# jtag-adapter-1-4.net
KiCad netlist of a schematic drawn in EAGLE
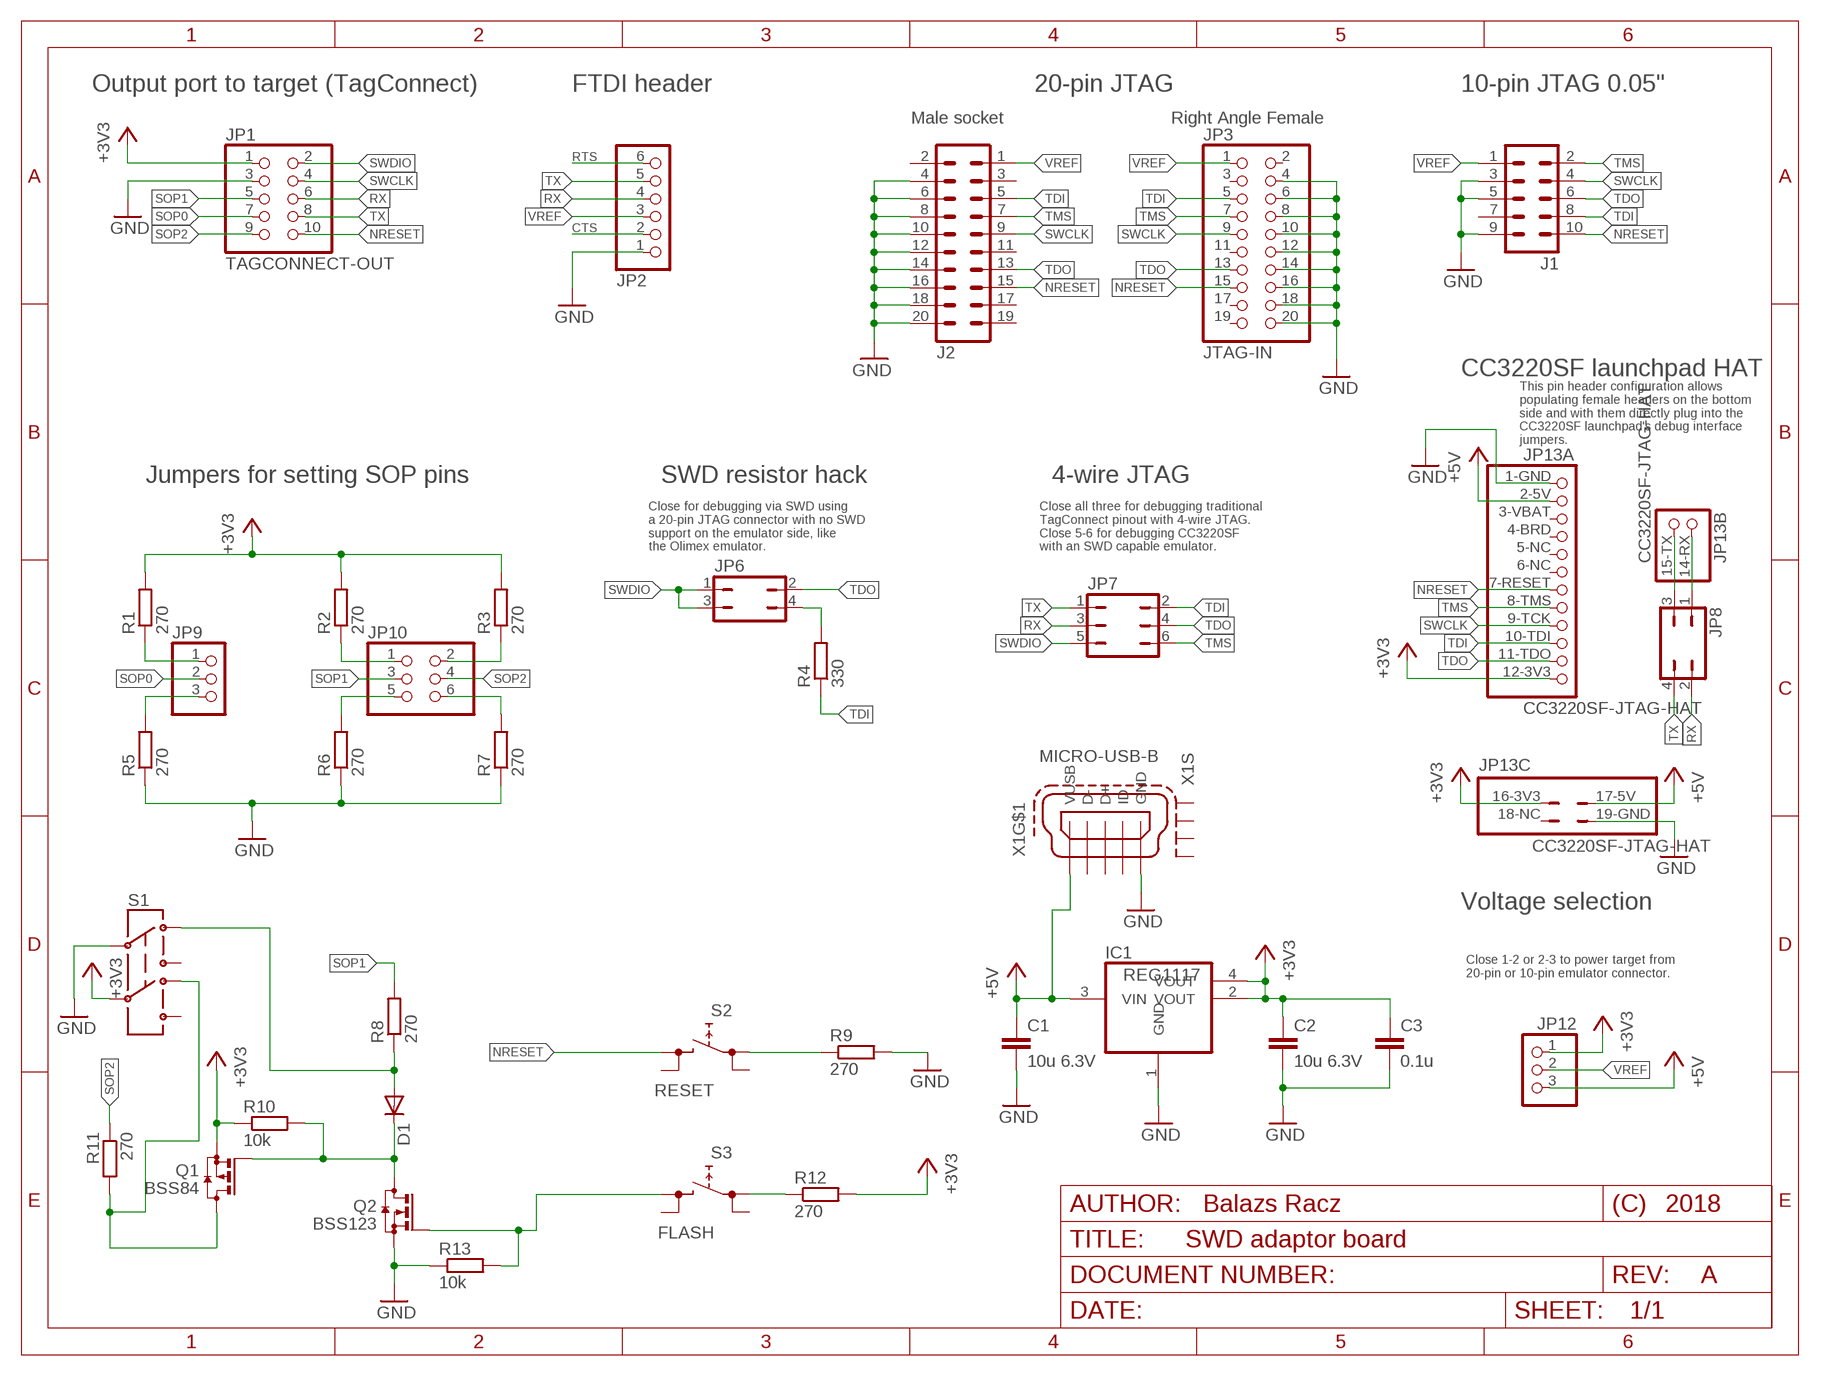
[diagram p0: schematic, sheet 1]

(export (version "E")
  (design (tool "Eeschema 10.0.6"))
  (components
    (comp (ref "C1")
      (value "10u 6.3V")
      (footprint "eagle-import:C0603K")
      (libsource (lib "eagle-import") (part "C-EUC0603K"))
    )
    (comp (ref "C2")
      (value "10u 6.3V")
      (footprint "eagle-import:C0603K")
      (libsource (lib "eagle-import") (part "C-EUC0603K"))
    )
    (comp (ref "C3")
      (value "0.1u")
      (footprint "eagle-import:C0603K")
      (libsource (lib "eagle-import") (part "C-EUC0603K"))
    )
    (comp (ref "D1")
      (value "DIODE-MINIMELF")
      (footprint "eagle-import:MINIMELF")
      (libsource (lib "eagle-import") (part "DIODE-MINIMELF"))
    )
    (comp (ref "IC1")
      (value "REG1117")
      (footprint "eagle-import:SOT223")
      (libsource (lib "eagle-import") (part "REG1117"))
    )
    (comp (ref "J1")
      (value "MA05-2_0.05X0.05")
      (footprint "eagle-import:MA05-2_0.05_X_0.05")
      (libsource (lib "eagle-import") (part "MA05-2_0.05X0.05"))
    )
    (comp (ref "J2")
      (value "MA10-2S")
      (footprint "eagle-import:MA10-2-SHROUDED")
      (libsource (lib "eagle-import") (part "MA10-2S"))
    )
    (comp (ref "JP1")
      (value "TAGCONNECT-OUT")
      (footprint "eagle-import:CON10M")
      (libsource (lib "eagle-import") (part "PINHD-2X5CN"))
    )
    (comp (ref "JP2")
      (value "PINHD-1X6")
      (footprint "eagle-import:1X06")
      (libsource (lib "eagle-import") (part "PINHD-1X6"))
    )
    (comp (ref "JP3")
      (value "JTAG-IN")
      (footprint "eagle-import:2X10_90")
      (libsource (lib "eagle-import") (part "PINHD-2X10/90"))
    )
    (comp (ref "JP6")
      (value "JP2Q")
      (footprint "eagle-import:JP2Q")
      (libsource (lib "eagle-import") (part "trainlib_JP2Q"))
    )
    (comp (ref "JP7")
      (value "JP3Q")
      (footprint "eagle-import:JP3Q")
      (libsource (lib "eagle-import") (part "JP3Q"))
    )
    (comp (ref "JP8")
      (value "JP2Q")
      (footprint "eagle-import:JP2Q")
      (libsource (lib "eagle-import") (part "JP2Q"))
    )
    (comp (ref "JP9")
      (value "PINHD-1X3")
      (footprint "eagle-import:1X03")
      (libsource (lib "eagle-import") (part "PINHD-1X3"))
    )
    (comp (ref "JP10")
      (value "PINHD-2X3")
      (footprint "eagle-import:2X03")
      (libsource (lib "eagle-import") (part "PINHD-2X3"))
    )
    (comp (ref "JP12")
      (value "PINHD-1X3")
      (footprint "eagle-import:1X03")
      (libsource (lib "eagle-import") (part "PINHD-1X3"))
    )
    (comp (ref "JP13")
      (value "CC3220SF-JTAG-HAT")
      (footprint "eagle-import:JTAG-LAUNCHPAD-3220SF")
      (libsource (lib "eagle-import") (part "CC3220SF-JTAG-HAT"))
    )
    (comp (ref "Q1")
      (value "BSS84")
      (footprint "eagle-import:SOT23")
      (libsource (lib "eagle-import") (part "BSS84"))
    )
    (comp (ref "Q2")
      (value "BSS123")
      (footprint "eagle-import:SOT23")
      (libsource (lib "eagle-import") (part "BSS123"))
    )
    (comp (ref "R1")
      (value "270")
      (footprint "eagle-import:R0805")
      (libsource (lib "eagle-import") (part "R-EU_R0805"))
    )
    (comp (ref "R2")
      (value "270")
      (footprint "eagle-import:R0805")
      (libsource (lib "eagle-import") (part "R-EU_R0805"))
    )
    (comp (ref "R3")
      (value "270")
      (footprint "eagle-import:R0805")
      (libsource (lib "eagle-import") (part "R-EU_R0805"))
    )
    (comp (ref "R4")
      (value "330")
      (footprint "eagle-import:R0805")
      (libsource (lib "eagle-import") (part "R-EU_R0805"))
    )
    (comp (ref "R5")
      (value "270")
      (footprint "eagle-import:R0805")
      (libsource (lib "eagle-import") (part "R-EU_R0805"))
    )
    (comp (ref "R6")
      (value "270")
      (footprint "eagle-import:R0805")
      (libsource (lib "eagle-import") (part "R-EU_R0805"))
    )
    (comp (ref "R7")
      (value "270")
      (footprint "eagle-import:R0805")
      (libsource (lib "eagle-import") (part "R-EU_R0805"))
    )
    (comp (ref "R8")
      (value "270")
      (footprint "eagle-import:R0805")
      (libsource (lib "eagle-import") (part "R-EU_R0805"))
    )
    (comp (ref "R9")
      (value "270")
      (footprint "eagle-import:R0805")
      (libsource (lib "eagle-import") (part "R-EU_R0805"))
    )
    (comp (ref "R10")
      (value "10k")
      (footprint "eagle-import:R0805")
      (libsource (lib "eagle-import") (part "R-EU_R0805"))
    )
    (comp (ref "R11")
      (value "270")
      (footprint "eagle-import:R0805")
      (libsource (lib "eagle-import") (part "R-EU_R0805"))
    )
    (comp (ref "R12")
      (value "270")
      (footprint "eagle-import:R0805")
      (libsource (lib "eagle-import") (part "R-EU_R0805"))
    )
    (comp (ref "R13")
      (value "10k")
      (footprint "eagle-import:R0805")
      (libsource (lib "eagle-import") (part "R-EU_R0805"))
    )
    (comp (ref "S1")
      (value "SWITCH-DPDTJS202011CQN")
      (footprint "eagle-import:DPDT-2.5X3.2MM")
      (libsource (lib "eagle-import") (part "SWITCH-DPDTJS202011CQN"))
    )
    (comp (ref "S2")
      (value "RESET")
      (footprint "eagle-import:TACTSW-6X6")
      (libsource (lib "eagle-import") (part "TACTSW-6X6S"))
    )
    (comp (ref "S3")
      (value "FLASH")
      (footprint "eagle-import:TACTSW-6X6")
      (libsource (lib "eagle-import") (part "TACTSW-6X6S"))
    )
    (comp (ref "X1")
      (value "MICRO-USB-B")
      (footprint "eagle-import:MICRO-B-PAC")
      (libsource (lib "eagle-import") (part "MICRO-USB-B"))
    )
  )
  (nets
    (net (code "1") (name "+3V3") (class "Default")
      (node (ref "C2") (pin "1") (pinfunction "1_1") (pintype "passive"))
      (node (ref "C3") (pin "1") (pinfunction "1_1") (pintype "passive"))
      (node (ref "IC1") (pin "2") (pinfunction "VOUT_2") (pintype "output"))
      (node (ref "IC1") (pin "4") (pinfunction "VOUT_4") (pintype "output"))
      (node (ref "JP1") (pin "1") (pinfunction "1_1") (pintype "passive"))
      (node (ref "JP12") (pin "1") (pinfunction "1_1") (pintype "passive"))
      (node (ref "JP13") (pin "12-3V3") (pinfunction "12_12-3V3") (pintype "passive"))
      (node (ref "JP13") (pin "16-3V3") (pinfunction "1_16-3V3") (pintype "passive"))
      (node (ref "Q1") (pin "2") (pinfunction "S_2") (pintype "passive"))
      (node (ref "R1") (pin "2") (pinfunction "2_2") (pintype "passive"))
      (node (ref "R10") (pin "1") (pinfunction "1_1") (pintype "passive"))
      (node (ref "R12") (pin "2") (pinfunction "2_2") (pintype "passive"))
      (node (ref "R2") (pin "2") (pinfunction "2_2") (pintype "passive"))
      (node (ref "R3") (pin "2") (pinfunction "2_2") (pintype "passive"))
      (node (ref "S1") (pin "5") (pinfunction "2C_5") (pintype "bidirectional"))
    )
    (net (code "2") (name "+5V") (class "Default")
      (node (ref "C1") (pin "1") (pinfunction "1_1") (pintype "passive"))
      (node (ref "IC1") (pin "3") (pinfunction "VIN_3") (pintype "input"))
      (node (ref "JP12") (pin "3") (pinfunction "3_3") (pintype "passive"))
      (node (ref "JP13") (pin "17-5V") (pinfunction "2_17-5V") (pintype "passive"))
      (node (ref "JP13") (pin "2-5V") (pinfunction "2_2-5V") (pintype "passive"))
      (node (ref "X1") (pin "1") (pinfunction "VUSB_1") (pintype "passive"))
    )
    (net (code "3") (name "/CTS") (class "Default")
      (node (ref "JP2") (pin "2") (pinfunction "2_2") (pintype "passive"))
    )
    (net (code "4") (name "/RTS") (class "Default")
      (node (ref "JP2") (pin "6") (pinfunction "6_6") (pintype "passive"))
    )
    (net (code "5") (name "GND") (class "Default")
      (node (ref "C1") (pin "2") (pinfunction "2_2") (pintype "passive"))
      (node (ref "C2") (pin "2") (pinfunction "2_2") (pintype "passive"))
      (node (ref "C3") (pin "2") (pinfunction "2_2") (pintype "passive"))
      (node (ref "IC1") (pin "1") (pinfunction "GND_1") (pintype "power_in"))
      (node (ref "J1") (pin "3") (pinfunction "3_3") (pintype "passive"))
      (node (ref "J1") (pin "5") (pinfunction "5_5") (pintype "passive"))
      (node (ref "J1") (pin "9") (pinfunction "9_9") (pintype "passive"))
      (node (ref "J2") (pin "10") (pinfunction "10_10") (pintype "passive"))
      (node (ref "J2") (pin "12") (pinfunction "12_12") (pintype "passive"))
      (node (ref "J2") (pin "14") (pinfunction "14_14") (pintype "passive"))
      (node (ref "J2") (pin "16") (pinfunction "16_16") (pintype "passive"))
      (node (ref "J2") (pin "18") (pinfunction "18_18") (pintype "passive"))
      (node (ref "J2") (pin "20") (pinfunction "20_20") (pintype "passive"))
      (node (ref "J2") (pin "4") (pinfunction "4_4") (pintype "passive"))
      (node (ref "J2") (pin "6") (pinfunction "6_6") (pintype "passive"))
      (node (ref "J2") (pin "8") (pinfunction "8_8") (pintype "passive"))
      (node (ref "JP1") (pin "3") (pinfunction "3_3") (pintype "passive"))
      (node (ref "JP13") (pin "1-GND") (pinfunction "1_1-GND") (pintype "passive"))
      (node (ref "JP13") (pin "19-GND") (pinfunction "4_19-GND") (pintype "passive"))
      (node (ref "JP2") (pin "1") (pinfunction "1_1") (pintype "passive"))
      (node (ref "JP3") (pin "10") (pinfunction "10_10") (pintype "passive"))
      (node (ref "JP3") (pin "12") (pinfunction "12_12") (pintype "passive"))
      (node (ref "JP3") (pin "14") (pinfunction "14_14") (pintype "passive"))
      (node (ref "JP3") (pin "16") (pinfunction "16_16") (pintype "passive"))
      (node (ref "JP3") (pin "18") (pinfunction "18_18") (pintype "passive"))
      (node (ref "JP3") (pin "20") (pinfunction "20_20") (pintype "passive"))
      (node (ref "JP3") (pin "4") (pinfunction "4_4") (pintype "passive"))
      (node (ref "JP3") (pin "6") (pinfunction "6_6") (pintype "passive"))
      (node (ref "JP3") (pin "8") (pinfunction "8_8") (pintype "passive"))
      (node (ref "Q2") (pin "2") (pinfunction "S_2") (pintype "passive"))
      (node (ref "R13") (pin "1") (pinfunction "1_1") (pintype "passive"))
      (node (ref "R5") (pin "1") (pinfunction "1_1") (pintype "passive"))
      (node (ref "R6") (pin "1") (pinfunction "1_1") (pintype "passive"))
      (node (ref "R7") (pin "1") (pinfunction "1_1") (pintype "passive"))
      (node (ref "R9") (pin "2") (pinfunction "2_2") (pintype "passive"))
      (node (ref "S1") (pin "2") (pinfunction "1C_2") (pintype "bidirectional"))
      (node (ref "X1") (pin "5") (pinfunction "GND_5") (pintype "passive"))
    )
    (net (code "6") (name "NRESET") (class "Default")
      (node (ref "J1") (pin "10") (pinfunction "10_10") (pintype "passive"))
      (node (ref "J2") (pin "15") (pinfunction "15_15") (pintype "passive"))
      (node (ref "JP1") (pin "10") (pinfunction "10_10") (pintype "passive"))
      (node (ref "JP13") (pin "7-RESET") (pinfunction "7_7-RESET") (pintype "passive"))
      (node (ref "JP3") (pin "15") (pinfunction "15_15") (pintype "passive"))
      (node (ref "S2") (pin "3") (pinfunction "2.1_3") (pintype "passive"))
    )
    (net (code "7") (name "Net-(JP6-Pad4)") (class "Default")
      (node (ref "JP6") (pin "4") (pinfunction "4_4") (pintype "passive"))
      (node (ref "R4") (pin "2") (pinfunction "2_2") (pintype "passive"))
    )
    (net (code "8") (name "Net-(JP9-Pad1)") (class "Default")
      (node (ref "JP9") (pin "1") (pinfunction "1_1") (pintype "passive"))
      (node (ref "R1") (pin "1") (pinfunction "1_1") (pintype "passive"))
    )
    (net (code "9") (name "Net-(JP9-Pad3)") (class "Default")
      (node (ref "JP9") (pin "3") (pinfunction "3_3") (pintype "passive"))
      (node (ref "R5") (pin "2") (pinfunction "2_2") (pintype "passive"))
    )
    (net (code "10") (name "Net-(JP10-Pad1)") (class "Default")
      (node (ref "JP10") (pin "1") (pinfunction "1_1") (pintype "passive"))
      (node (ref "R2") (pin "1") (pinfunction "1_1") (pintype "passive"))
    )
    (net (code "11") (name "Net-(JP10-Pad2)") (class "Default")
      (node (ref "JP10") (pin "2") (pinfunction "2_2") (pintype "passive"))
      (node (ref "R3") (pin "1") (pinfunction "1_1") (pintype "passive"))
    )
    (net (code "12") (name "Net-(JP10-Pad5)") (class "Default")
      (node (ref "JP10") (pin "5") (pinfunction "5_5") (pintype "passive"))
      (node (ref "R6") (pin "2") (pinfunction "2_2") (pintype "passive"))
    )
    (net (code "13") (name "Net-(JP10-Pad6)") (class "Default")
      (node (ref "JP10") (pin "6") (pinfunction "6_6") (pintype "passive"))
      (node (ref "R7") (pin "2") (pinfunction "2_2") (pintype "passive"))
    )
    (net (code "14") (name "Net-(JP13B-1)") (class "Default")
      (node (ref "JP13") (pin "14-RX") (pinfunction "1_14-RX") (pintype "passive"))
      (node (ref "JP8") (pin "1") (pinfunction "1_1") (pintype "passive"))
    )
    (net (code "15") (name "Net-(JP13B-2)") (class "Default")
      (node (ref "JP13") (pin "15-TX") (pinfunction "2_15-TX") (pintype "passive"))
      (node (ref "JP8") (pin "3") (pinfunction "3_3") (pintype "passive"))
    )
    (net (code "16") (name "Net-(Q1-D)") (class "Default")
      (node (ref "Q1") (pin "3") (pinfunction "D_3") (pintype "passive"))
      (node (ref "R11") (pin "2") (pinfunction "2_2") (pintype "passive"))
      (node (ref "S1") (pin "4") (pinfunction "2A_4") (pintype "bidirectional"))
    )
    (net (code "17") (name "Net-(Q1-G)") (class "Default")
      (node (ref "D1") (pin "C") (pinfunction "C_C") (pintype "passive"))
      (node (ref "Q1") (pin "1") (pinfunction "G_1") (pintype "passive"))
      (node (ref "Q2") (pin "3") (pinfunction "D_3") (pintype "passive"))
      (node (ref "R10") (pin "2") (pinfunction "2_2") (pintype "passive"))
    )
    (net (code "18") (name "Net-(Q2-G)") (class "Default")
      (node (ref "Q2") (pin "1") (pinfunction "G_1") (pintype "passive"))
      (node (ref "R13") (pin "2") (pinfunction "2_2") (pintype "passive"))
      (node (ref "S3") (pin "3") (pinfunction "2.1_3") (pintype "passive"))
    )
    (net (code "19") (name "Net-(S1-1A)") (class "Default")
      (node (ref "D1") (pin "A") (pinfunction "A_A") (pintype "passive"))
      (node (ref "R8") (pin "1") (pinfunction "1_1") (pintype "passive"))
      (node (ref "S1") (pin "1") (pinfunction "1A_1") (pintype "bidirectional"))
    )
    (net (code "20") (name "Net-(S2-1.1)") (class "Default")
      (node (ref "R9") (pin "1") (pinfunction "1_1") (pintype "passive"))
      (node (ref "S2") (pin "1") (pinfunction "1.1_1") (pintype "passive"))
    )
    (net (code "21") (name "Net-(S3-1.1)") (class "Default")
      (node (ref "R12") (pin "1") (pinfunction "1_1") (pintype "passive"))
      (node (ref "S3") (pin "1") (pinfunction "1.1_1") (pintype "passive"))
    )
    (net (code "22") (name "RX") (class "Default")
      (node (ref "JP1") (pin "6") (pinfunction "6_6") (pintype "passive"))
      (node (ref "JP2") (pin "4") (pinfunction "4_4") (pintype "passive"))
      (node (ref "JP7") (pin "3") (pinfunction "3_3") (pintype "passive"))
      (node (ref "JP8") (pin "2") (pinfunction "2_2") (pintype "passive"))
    )
    (net (code "23") (name "SOP0") (class "Default")
      (node (ref "JP1") (pin "7") (pinfunction "7_7") (pintype "passive"))
      (node (ref "JP9") (pin "2") (pinfunction "2_2") (pintype "passive"))
    )
    (net (code "24") (name "SOP1") (class "Default")
      (node (ref "JP1") (pin "5") (pinfunction "5_5") (pintype "passive"))
      (node (ref "JP10") (pin "3") (pinfunction "3_3") (pintype "passive"))
      (node (ref "R8") (pin "2") (pinfunction "2_2") (pintype "passive"))
    )
    (net (code "25") (name "SOP2") (class "Default")
      (node (ref "JP1") (pin "9") (pinfunction "9_9") (pintype "passive"))
      (node (ref "JP10") (pin "4") (pinfunction "4_4") (pintype "passive"))
      (node (ref "R11") (pin "1") (pinfunction "1_1") (pintype "passive"))
    )
    (net (code "26") (name "SWCLK") (class "Default")
      (node (ref "J1") (pin "4") (pinfunction "4_4") (pintype "passive"))
      (node (ref "J2") (pin "9") (pinfunction "9_9") (pintype "passive"))
      (node (ref "JP1") (pin "4") (pinfunction "4_4") (pintype "passive"))
      (node (ref "JP13") (pin "9-TCK") (pinfunction "9_9-TCK") (pintype "passive"))
      (node (ref "JP3") (pin "9") (pinfunction "9_9") (pintype "passive"))
    )
    (net (code "27") (name "SWDIO") (class "Default")
      (node (ref "JP1") (pin "2") (pinfunction "2_2") (pintype "passive"))
      (node (ref "JP6") (pin "1") (pinfunction "1_1") (pintype "passive"))
      (node (ref "JP6") (pin "3") (pinfunction "3_3") (pintype "passive"))
      (node (ref "JP7") (pin "5") (pinfunction "5_5") (pintype "passive"))
    )
    (net (code "28") (name "TDI") (class "Default")
      (node (ref "J1") (pin "8") (pinfunction "8_8") (pintype "passive"))
      (node (ref "J2") (pin "5") (pinfunction "5_5") (pintype "passive"))
      (node (ref "JP13") (pin "10-TDI") (pinfunction "10_10-TDI") (pintype "passive"))
      (node (ref "JP3") (pin "5") (pinfunction "5_5") (pintype "passive"))
      (node (ref "JP7") (pin "2") (pinfunction "2_2") (pintype "passive"))
      (node (ref "R4") (pin "1") (pinfunction "1_1") (pintype "passive"))
    )
    (net (code "29") (name "TDO") (class "Default")
      (node (ref "J1") (pin "6") (pinfunction "6_6") (pintype "passive"))
      (node (ref "J2") (pin "13") (pinfunction "13_13") (pintype "passive"))
      (node (ref "JP13") (pin "11-TDO") (pinfunction "11_11-TDO") (pintype "passive"))
      (node (ref "JP3") (pin "13") (pinfunction "13_13") (pintype "passive"))
      (node (ref "JP6") (pin "2") (pinfunction "2_2") (pintype "passive"))
      (node (ref "JP7") (pin "4") (pinfunction "4_4") (pintype "passive"))
    )
    (net (code "30") (name "TMS") (class "Default")
      (node (ref "J1") (pin "2") (pinfunction "2_2") (pintype "passive"))
      (node (ref "J2") (pin "7") (pinfunction "7_7") (pintype "passive"))
      (node (ref "JP13") (pin "8-TMS") (pinfunction "8_8-TMS") (pintype "passive"))
      (node (ref "JP3") (pin "7") (pinfunction "7_7") (pintype "passive"))
      (node (ref "JP7") (pin "6") (pinfunction "6_6") (pintype "passive"))
    )
    (net (code "31") (name "TX") (class "Default")
      (node (ref "JP1") (pin "8") (pinfunction "8_8") (pintype "passive"))
      (node (ref "JP2") (pin "5") (pinfunction "5_5") (pintype "passive"))
      (node (ref "JP7") (pin "1") (pinfunction "1_1") (pintype "passive"))
      (node (ref "JP8") (pin "4") (pinfunction "4_4") (pintype "passive"))
    )
    (net (code "32") (name "VREF") (class "Default")
      (node (ref "J1") (pin "1") (pinfunction "1_1") (pintype "passive"))
      (node (ref "J2") (pin "1") (pinfunction "1_1") (pintype "passive"))
      (node (ref "JP12") (pin "2") (pinfunction "2_2") (pintype "passive"))
      (node (ref "JP2") (pin "3") (pinfunction "3_3") (pintype "passive"))
      (node (ref "JP3") (pin "1") (pinfunction "1_1") (pintype "passive"))
    )
    (net (code "33") (name "unconnected-(J1-Pad7)") (class "Default")
      (node (ref "J1") (pin "7") (pinfunction "7_7") (pintype "passive"))
    )
    (net (code "34") (name "unconnected-(J2-Pad2)") (class "Default")
      (node (ref "J2") (pin "2") (pinfunction "2_2") (pintype "passive"))
    )
    (net (code "35") (name "unconnected-(J2-Pad3)") (class "Default")
      (node (ref "J2") (pin "3") (pinfunction "3_3") (pintype "passive"))
    )
    (net (code "36") (name "unconnected-(J2-Pad11)") (class "Default")
      (node (ref "J2") (pin "11") (pinfunction "11_11") (pintype "passive"))
    )
    (net (code "37") (name "unconnected-(J2-Pad17)") (class "Default")
      (node (ref "J2") (pin "17") (pinfunction "17_17") (pintype "passive"))
    )
    (net (code "38") (name "unconnected-(J2-Pad19)") (class "Default")
      (node (ref "J2") (pin "19") (pinfunction "19_19") (pintype "passive"))
    )
    (net (code "39") (name "unconnected-(JP3-Pad2)") (class "Default")
      (node (ref "JP3") (pin "2") (pinfunction "2_2") (pintype "passive"))
    )
    (net (code "40") (name "unconnected-(JP3-Pad3)") (class "Default")
      (node (ref "JP3") (pin "3") (pinfunction "3_3") (pintype "passive"))
    )
    (net (code "41") (name "unconnected-(JP3-Pad11)") (class "Default")
      (node (ref "JP3") (pin "11") (pinfunction "11_11") (pintype "passive"))
    )
    (net (code "42") (name "unconnected-(JP3-Pad17)") (class "Default")
      (node (ref "JP3") (pin "17") (pinfunction "17_17") (pintype "passive"))
    )
    (net (code "43") (name "unconnected-(JP3-Pad19)") (class "Default")
      (node (ref "JP3") (pin "19") (pinfunction "19_19") (pintype "passive"))
    )
    (net (code "44") (name "unconnected-(JP13A-3-Pad3-VBAT)") (class "Default")
      (node (ref "JP13") (pin "3-VBAT") (pinfunction "3_3-VBAT") (pintype "passive"))
    )
    (net (code "45") (name "unconnected-(JP13A-4-Pad4-BRD)") (class "Default")
      (node (ref "JP13") (pin "4-BRD") (pinfunction "4_4-BRD") (pintype "passive"))
    )
    (net (code "46") (name "unconnected-(JP13A-5-Pad5-NC)") (class "Default")
      (node (ref "JP13") (pin "5-NC") (pinfunction "5_5-NC") (pintype "passive"))
    )
    (net (code "47") (name "unconnected-(JP13A-6-Pad6-NC)") (class "Default")
      (node (ref "JP13") (pin "6-NC") (pinfunction "6_6-NC") (pintype "passive"))
    )
    (net (code "48") (name "unconnected-(JP13C-3-Pad18-NC)") (class "Default")
      (node (ref "JP13") (pin "18-NC") (pinfunction "3_18-NC") (pintype "passive"))
    )
    (net (code "49") (name "unconnected-(S1-1B-Pad3)") (class "Default")
      (node (ref "S1") (pin "3") (pinfunction "1B_3") (pintype "bidirectional"))
    )
    (net (code "50") (name "unconnected-(S1-2B-Pad6)") (class "Default")
      (node (ref "S1") (pin "6") (pinfunction "2B_6") (pintype "bidirectional"))
    )
    (net (code "51") (name "unconnected-(S2-1.2-Pad2)") (class "Default")
      (node (ref "S2") (pin "2") (pinfunction "1.2_2") (pintype "passive"))
    )
    (net (code "52") (name "unconnected-(S2-2.2-Pad4)") (class "Default")
      (node (ref "S2") (pin "4") (pinfunction "2.2_4") (pintype "passive"))
    )
    (net (code "53") (name "unconnected-(S3-1.2-Pad2)") (class "Default")
      (node (ref "S3") (pin "2") (pinfunction "1.2_2") (pintype "passive"))
    )
    (net (code "54") (name "unconnected-(S3-2.2-Pad4)") (class "Default")
      (node (ref "S3") (pin "4") (pinfunction "2.2_4") (pintype "passive"))
    )
    (net (code "55") (name "unconnected-(X1A-D+-Pad3)") (class "Default")
      (node (ref "X1") (pin "3") (pinfunction "D+_3") (pintype "passive"))
    )
    (net (code "56") (name "unconnected-(X1A-D--Pad2)") (class "Default")
      (node (ref "X1") (pin "2") (pinfunction "D-_2") (pintype "passive"))
    )
    (net (code "57") (name "unconnected-(X1A-ID-Pad4)") (class "Default")
      (node (ref "X1") (pin "4") (pinfunction "ID_4") (pintype "passive"))
    )
    (net (code "58") (name "unconnected-(X1B-S1-PadM1)") (class "Default")
      (node (ref "X1") (pin "M1") (pinfunction "S1_M1") (pintype "passive"))
    )
    (net (code "59") (name "unconnected-(X1B-S2-PadM2)") (class "Default")
      (node (ref "X1") (pin "M2") (pinfunction "S2_M2") (pintype "passive"))
    )
    (net (code "60") (name "unconnected-(X1B-S3-PadM3)") (class "Default")
      (node (ref "X1") (pin "M3") (pinfunction "S3_M3") (pintype "passive"))
    )
    (net (code "61") (name "unconnected-(X1B-S4-PadM4)") (class "Default")
      (node (ref "X1") (pin "M4") (pinfunction "S4_M4") (pintype "passive"))
    )
  )
)
